# recepteurRF.net
KiCad netlist of a schematic drawn in EAGLE
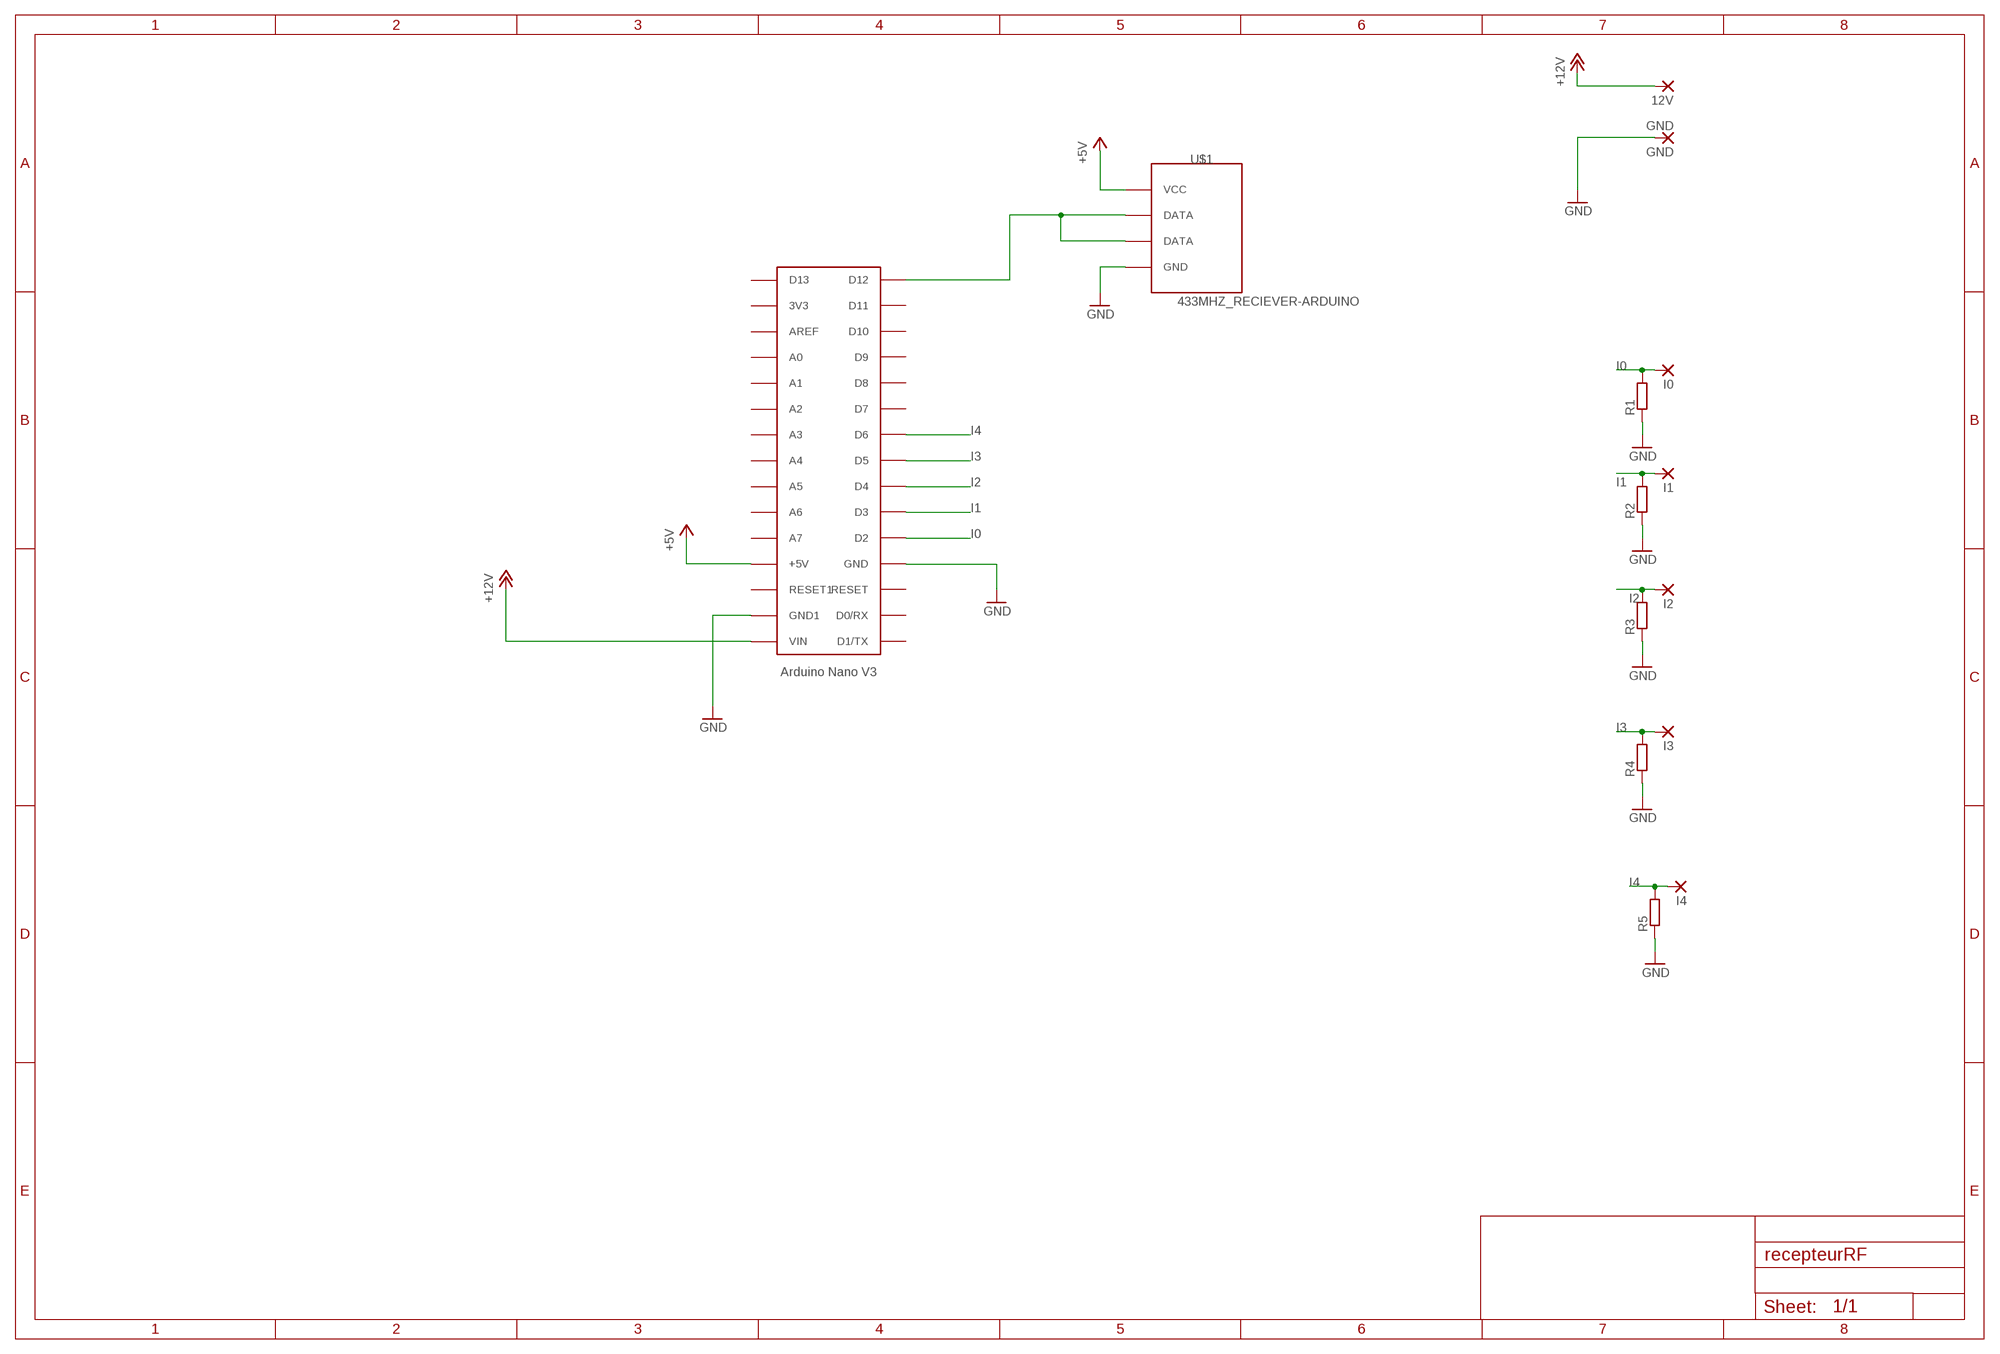
[diagram p0: schematic, sheet 1]

(export (version "E")
  (design (tool "Eeschema 10.0.6"))
  (components
    (comp (ref "12V")
      (value "SMD5")
      (footprint "eagle-import:SMD2,54-5,08")
      (libsource (lib "eagle-import") (part "SMD5"))
    )
    (comp (ref "GND")
      (value "GND")
      (footprint "eagle-import:SMD2,54-5,08")
      (libsource (lib "eagle-import") (part "SMD5"))
    )
    (comp (ref "I0")
      (value "SMD5")
      (footprint "eagle-import:SMD2,54-5,08")
      (libsource (lib "eagle-import") (part "SMD5"))
    )
    (comp (ref "I1")
      (value "SMD5")
      (footprint "eagle-import:SMD2,54-5,08")
      (libsource (lib "eagle-import") (part "SMD5"))
    )
    (comp (ref "I2")
      (value "SMD5")
      (footprint "eagle-import:SMD2,54-5,08")
      (libsource (lib "eagle-import") (part "SMD5"))
    )
    (comp (ref "I3")
      (value "SMD5")
      (footprint "eagle-import:SMD2,54-5,08")
      (libsource (lib "eagle-import") (part "SMD5"))
    )
    (comp (ref "I4")
      (value "SMD5")
      (footprint "eagle-import:SMD2,54-5,08")
      (libsource (lib "eagle-import") (part "SMD5"))
    )
    (comp (ref "R1")
      (value "R-EU_R1206")
      (footprint "eagle-import:R1206")
      (libsource (lib "eagle-import") (part "R-EU_R1206"))
    )
    (comp (ref "R2")
      (value "R-EU_R1206")
      (footprint "eagle-import:R1206")
      (libsource (lib "eagle-import") (part "R-EU_R1206"))
    )
    (comp (ref "R3")
      (value "R-EU_R1206")
      (footprint "eagle-import:R1206")
      (libsource (lib "eagle-import") (part "R-EU_R1206"))
    )
    (comp (ref "R4")
      (value "R-EU_R1206")
      (footprint "eagle-import:R1206")
      (libsource (lib "eagle-import") (part "R-EU_R1206"))
    )
    (comp (ref "R5")
      (value "R-EU_R1206")
      (footprint "eagle-import:R1206")
      (libsource (lib "eagle-import") (part "R-EU_R1206"))
    )
    (comp (ref "U$1")
      (value "433MHZ_RECIEVER-ARDUINO")
      (footprint "eagle-import:433MHZ_RECIEVER-ARDUINO")
      (libsource (lib "eagle-import") (part "433MHZ_RECIEVER-ARDUINO"))
    )
    (comp (ref "U$2")
      (value "ARDUINONANO")
      (footprint "eagle-import:PDIP-32")
      (libsource (lib "eagle-import") (part "ARDUINONANO"))
    )
  )
  (nets
    (net (code "1") (name "+5V") (class "Default")
      (node (ref "U$1") (pin "VCC") (pinfunction "VCC_VCC") (pintype "bidirectional"))
      (node (ref "U$2") (pin "+5V") (pinfunction "+5V_+5V") (pintype "bidirectional"))
    )
    (net (code "2") (name "+12V") (class "Default")
      (node (ref "12V") (pin "1") (pinfunction "P_1") (pintype "passive"))
      (node (ref "U$2") (pin "VIN") (pinfunction "VIN_VIN") (pintype "bidirectional"))
    )
    (net (code "3") (name "/I0") (class "Default")
      (node (ref "I0") (pin "1") (pinfunction "P_1") (pintype "passive"))
      (node (ref "R1") (pin "2") (pinfunction "2_2") (pintype "passive"))
      (node (ref "U$2") (pin "D2") (pinfunction "D2_D2") (pintype "bidirectional"))
    )
    (net (code "4") (name "/I1") (class "Default")
      (node (ref "I1") (pin "1") (pinfunction "P_1") (pintype "passive"))
      (node (ref "R2") (pin "2") (pinfunction "2_2") (pintype "passive"))
      (node (ref "U$2") (pin "D3") (pinfunction "D3_D3") (pintype "bidirectional"))
    )
    (net (code "5") (name "/I2") (class "Default")
      (node (ref "I2") (pin "1") (pinfunction "P_1") (pintype "passive"))
      (node (ref "R3") (pin "2") (pinfunction "2_2") (pintype "passive"))
      (node (ref "U$2") (pin "D4") (pinfunction "D4_D4") (pintype "bidirectional"))
    )
    (net (code "6") (name "/I3") (class "Default")
      (node (ref "I3") (pin "1") (pinfunction "P_1") (pintype "passive"))
      (node (ref "R4") (pin "2") (pinfunction "2_2") (pintype "passive"))
      (node (ref "U$2") (pin "D5") (pinfunction "D5_D5") (pintype "bidirectional"))
    )
    (net (code "7") (name "/I4") (class "Default")
      (node (ref "I4") (pin "1") (pinfunction "P_1") (pintype "passive"))
      (node (ref "R5") (pin "2") (pinfunction "2_2") (pintype "passive"))
      (node (ref "U$2") (pin "D6") (pinfunction "D6_D6") (pintype "bidirectional"))
    )
    (net (code "8") (name "GND") (class "Default")
      (node (ref "GND") (pin "1") (pinfunction "P_1") (pintype "passive"))
      (node (ref "R1") (pin "1") (pinfunction "1_1") (pintype "passive"))
      (node (ref "R2") (pin "1") (pinfunction "1_1") (pintype "passive"))
      (node (ref "R3") (pin "1") (pinfunction "1_1") (pintype "passive"))
      (node (ref "R4") (pin "1") (pinfunction "1_1") (pintype "passive"))
      (node (ref "R5") (pin "1") (pinfunction "1_1") (pintype "passive"))
      (node (ref "U$1") (pin "GND") (pinfunction "GND_GND") (pintype "bidirectional"))
      (node (ref "U$2") (pin "GND") (pinfunction "GND_GND") (pintype "bidirectional"))
      (node (ref "U$2") (pin "GND1") (pinfunction "GND1_GND1") (pintype "bidirectional"))
    )
    (net (code "9") (name "Net-(U$1-DATA-PadDATA@0)") (class "Default")
      (node (ref "U$1") (pin "DATA@0") (pinfunction "DATA_DATA@0") (pintype "bidirectional"))
      (node (ref "U$1") (pin "DATA@1") (pinfunction "DATA_DATA@1") (pintype "bidirectional"))
      (node (ref "U$2") (pin "D12") (pinfunction "D12_D12") (pintype "bidirectional"))
    )
    (net (code "10") (name "unconnected-(U$2-A0-PadA7)") (class "Default")
      (node (ref "U$2") (pin "A7") (pinfunction "A0_A7") (pintype "bidirectional"))
    )
    (net (code "11") (name "unconnected-(U$2-A1-PadA6)") (class "Default")
      (node (ref "U$2") (pin "A6") (pinfunction "A1_A6") (pintype "bidirectional"))
    )
    (net (code "12") (name "unconnected-(U$2-A2-PadA5)") (class "Default")
      (node (ref "U$2") (pin "A5") (pinfunction "A2_A5") (pintype "bidirectional"))
    )
    (net (code "13") (name "unconnected-(U$2-A3-PadA4)") (class "Default")
      (node (ref "U$2") (pin "A4") (pinfunction "A3_A4") (pintype "bidirectional"))
    )
    (net (code "14") (name "unconnected-(U$2-A4-PadA3)") (class "Default")
      (node (ref "U$2") (pin "A3") (pinfunction "A4_A3") (pintype "bidirectional"))
    )
    (net (code "15") (name "unconnected-(U$2-A5-PadA2)") (class "Default")
      (node (ref "U$2") (pin "A2") (pinfunction "A5_A2") (pintype "bidirectional"))
    )
    (net (code "16") (name "unconnected-(U$2-A6-PadA1)") (class "Default")
      (node (ref "U$2") (pin "A1") (pinfunction "A6_A1") (pintype "bidirectional"))
    )
    (net (code "17") (name "unconnected-(U$2-A7-PadA0)") (class "Default")
      (node (ref "U$2") (pin "A0") (pinfunction "A7_A0") (pintype "bidirectional"))
    )
    (net (code "18") (name "unconnected-(U$2-Pad3V3)") (class "Default")
      (node (ref "U$2") (pin "3V3") (pinfunction "3V3_3V3") (pintype "bidirectional"))
    )
    (net (code "19") (name "unconnected-(U$2-PadAREF)") (class "Default")
      (node (ref "U$2") (pin "AREF") (pinfunction "AREF_AREF") (pintype "bidirectional"))
    )
    (net (code "20") (name "unconnected-(U$2-PadD0{slash}RX)") (class "Default")
      (node (ref "U$2") (pin "D0/RX") (pinfunction "D0/RX_D0/RX") (pintype "bidirectional"))
    )
    (net (code "21") (name "unconnected-(U$2-PadD1{slash}TX)") (class "Default")
      (node (ref "U$2") (pin "D1/TX") (pinfunction "D1/TX_D1/TX") (pintype "bidirectional"))
    )
    (net (code "22") (name "unconnected-(U$2-PadD7)") (class "Default")
      (node (ref "U$2") (pin "D7") (pinfunction "D7_D7") (pintype "bidirectional"))
    )
    (net (code "23") (name "unconnected-(U$2-PadD8)") (class "Default")
      (node (ref "U$2") (pin "D8") (pinfunction "D8_D8") (pintype "bidirectional"))
    )
    (net (code "24") (name "unconnected-(U$2-PadD9)") (class "Default")
      (node (ref "U$2") (pin "D9") (pinfunction "D9_D9") (pintype "bidirectional"))
    )
    (net (code "25") (name "unconnected-(U$2-PadD10)") (class "Default")
      (node (ref "U$2") (pin "D10") (pinfunction "D10_D10") (pintype "bidirectional"))
    )
    (net (code "26") (name "unconnected-(U$2-PadD11)") (class "Default")
      (node (ref "U$2") (pin "D11") (pinfunction "D11_D11") (pintype "bidirectional"))
    )
    (net (code "27") (name "unconnected-(U$2-PadD13)") (class "Default")
      (node (ref "U$2") (pin "D13") (pinfunction "D13_D13") (pintype "bidirectional"))
    )
    (net (code "28") (name "unconnected-(U$2-PadRESET)") (class "Default")
      (node (ref "U$2") (pin "RESET") (pinfunction "RESET_RESET") (pintype "bidirectional"))
    )
    (net (code "29") (name "unconnected-(U$2-PadRESET1)") (class "Default")
      (node (ref "U$2") (pin "RESET1") (pinfunction "RESET1_RESET1") (pintype "bidirectional"))
    )
  )
)
